# ShifterDial.net
KiCad netlist of a schematic drawn in EAGLE
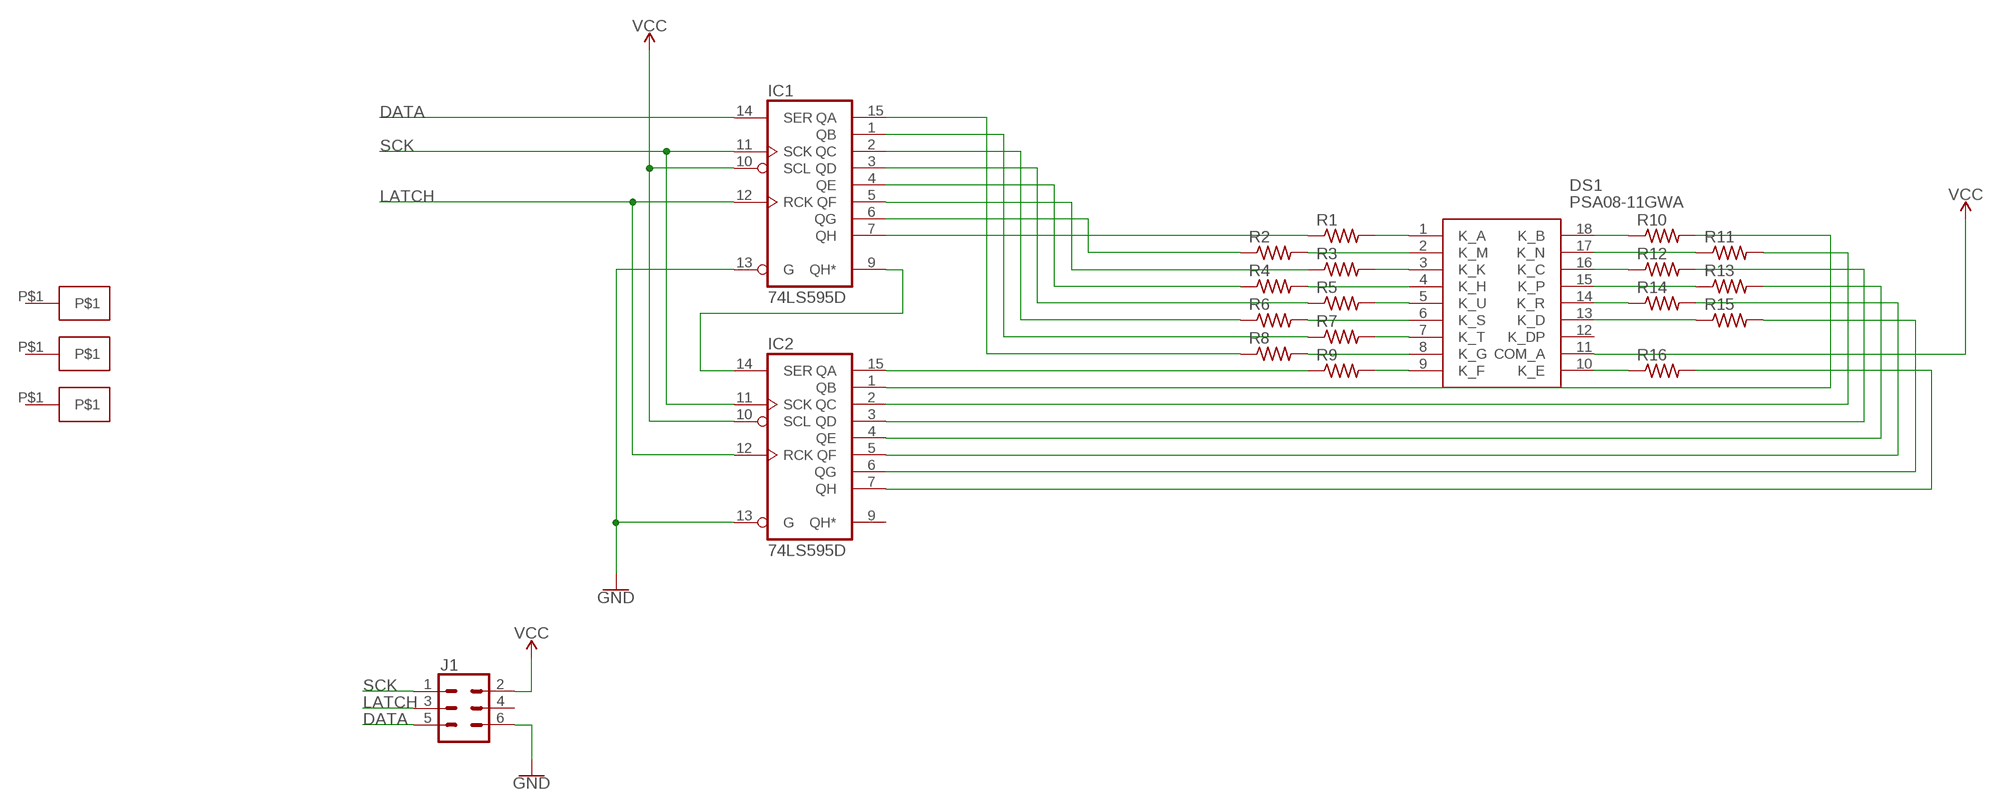
[diagram p0: schematic, sheet 1]

(export (version "E")
  (design (tool "Eeschema 10.0.6"))
  (components
    (comp (ref "DS1")
      (value "PSA08-11GWA")
      (footprint "eagle-import:PSA0811GWA")
      (fields (field (name "MOUSER_PART_NUMBER") "604-PSA08-11GWA"))
      (libsource (lib "eagle-import") (part "PSA08-11GWA"))
    )
    (comp (ref "IC1")
      (value "74LS595D")
      (footprint "eagle-import:SO16")
      (libsource (lib "eagle-import") (part "74595DLS"))
    )
    (comp (ref "IC2")
      (value "74LS595D")
      (footprint "eagle-import:SO16")
      (libsource (lib "eagle-import") (part "74595DLS"))
    )
    (comp (ref "J1")
      (value "CONN_03X2SHROUD")
      (footprint "eagle-import:2X3-SHROUDED")
      (libsource (lib "eagle-import") (part "CONN_03X2SHROUD"))
    )
    (comp (ref "R1")
      (value "R-US_R0603")
      (footprint "eagle-import:R0603")
      (libsource (lib "eagle-import") (part "R-US_R0603"))
    )
    (comp (ref "R2")
      (value "R-US_R0603")
      (footprint "eagle-import:R0603")
      (libsource (lib "eagle-import") (part "R-US_R0603"))
    )
    (comp (ref "R3")
      (value "R-US_R0603")
      (footprint "eagle-import:R0603")
      (libsource (lib "eagle-import") (part "R-US_R0603"))
    )
    (comp (ref "R4")
      (value "R-US_R0603")
      (footprint "eagle-import:R0603")
      (libsource (lib "eagle-import") (part "R-US_R0603"))
    )
    (comp (ref "R5")
      (value "R-US_R0603")
      (footprint "eagle-import:R0603")
      (libsource (lib "eagle-import") (part "R-US_R0603"))
    )
    (comp (ref "R6")
      (value "R-US_R0603")
      (footprint "eagle-import:R0603")
      (libsource (lib "eagle-import") (part "R-US_R0603"))
    )
    (comp (ref "R7")
      (value "R-US_R0603")
      (footprint "eagle-import:R0603")
      (libsource (lib "eagle-import") (part "R-US_R0603"))
    )
    (comp (ref "R8")
      (value "R-US_R0603")
      (footprint "eagle-import:R0603")
      (libsource (lib "eagle-import") (part "R-US_R0603"))
    )
    (comp (ref "R9")
      (value "R-US_R0603")
      (footprint "eagle-import:R0603")
      (libsource (lib "eagle-import") (part "R-US_R0603"))
    )
    (comp (ref "R10")
      (value "R-US_R0603")
      (footprint "eagle-import:R0603")
      (libsource (lib "eagle-import") (part "R-US_R0603"))
    )
    (comp (ref "R11")
      (value "R-US_R0603")
      (footprint "eagle-import:R0603")
      (libsource (lib "eagle-import") (part "R-US_R0603"))
    )
    (comp (ref "R12")
      (value "R-US_R0603")
      (footprint "eagle-import:R0603")
      (libsource (lib "eagle-import") (part "R-US_R0603"))
    )
    (comp (ref "R13")
      (value "R-US_R0603")
      (footprint "eagle-import:R0603")
      (libsource (lib "eagle-import") (part "R-US_R0603"))
    )
    (comp (ref "R14")
      (value "R-US_R0603")
      (footprint "eagle-import:R0603")
      (libsource (lib "eagle-import") (part "R-US_R0603"))
    )
    (comp (ref "R15")
      (value "R-US_R0603")
      (footprint "eagle-import:R0603")
      (libsource (lib "eagle-import") (part "R-US_R0603"))
    )
    (comp (ref "R16")
      (value "R-US_R0603")
      (footprint "eagle-import:R0603")
      (libsource (lib "eagle-import") (part "R-US_R0603"))
    )
    (comp (ref "U$1")
      (value "KEYSTONEM3")
      (footprint "eagle-import:M3SMDSTANDOFF")
      (libsource (lib "eagle-import") (part "KEYSTONEM3"))
    )
    (comp (ref "U$2")
      (value "KEYSTONEM3")
      (footprint "eagle-import:M3SMDSTANDOFF")
      (libsource (lib "eagle-import") (part "KEYSTONEM3"))
    )
    (comp (ref "U$3")
      (value "KEYSTONEM3")
      (footprint "eagle-import:M3SMDSTANDOFF")
      (libsource (lib "eagle-import") (part "KEYSTONEM3"))
    )
  )
  (nets
    (net (code "1") (name "/DATA") (class "Default")
      (node (ref "IC1") (pin "14") (pinfunction "SER_14") (pintype "input"))
      (node (ref "J1") (pin "5") (pinfunction "5_5") (pintype "bidirectional"))
    )
    (net (code "2") (name "/LATCH") (class "Default")
      (node (ref "IC1") (pin "12") (pinfunction "RCK_12") (pintype "input"))
      (node (ref "IC2") (pin "12") (pinfunction "RCK_12") (pintype "input"))
      (node (ref "J1") (pin "3") (pinfunction "3_3") (pintype "bidirectional"))
    )
    (net (code "3") (name "/SCK") (class "Default")
      (node (ref "IC1") (pin "11") (pinfunction "SCK_11") (pintype "input"))
      (node (ref "IC2") (pin "11") (pinfunction "SCK_11") (pintype "input"))
      (node (ref "J1") (pin "1") (pinfunction "1_1") (pintype "bidirectional"))
    )
    (net (code "4") (name "GND") (class "Default")
      (node (ref "IC1") (pin "13") (pinfunction "G_13") (pintype "input"))
      (node (ref "IC2") (pin "13") (pinfunction "G_13") (pintype "input"))
      (node (ref "J1") (pin "6") (pinfunction "6_6") (pintype "bidirectional"))
    )
    (net (code "5") (name "Net-(DS1-K_A)") (class "Default")
      (node (ref "DS1") (pin "1") (pinfunction "K_A_1") (pintype "bidirectional"))
      (node (ref "R1") (pin "2") (pinfunction "2_2") (pintype "passive"))
    )
    (net (code "6") (name "Net-(DS1-K_B)") (class "Default")
      (node (ref "DS1") (pin "18") (pinfunction "K_B_18") (pintype "bidirectional"))
      (node (ref "R10") (pin "1") (pinfunction "1_1") (pintype "passive"))
    )
    (net (code "7") (name "Net-(DS1-K_C)") (class "Default")
      (node (ref "DS1") (pin "16") (pinfunction "K_C_16") (pintype "bidirectional"))
      (node (ref "R12") (pin "1") (pinfunction "1_1") (pintype "passive"))
    )
    (net (code "8") (name "Net-(DS1-K_D)") (class "Default")
      (node (ref "DS1") (pin "13") (pinfunction "K_D_13") (pintype "bidirectional"))
      (node (ref "R15") (pin "1") (pinfunction "1_1") (pintype "passive"))
    )
    (net (code "9") (name "Net-(DS1-K_E)") (class "Default")
      (node (ref "DS1") (pin "10") (pinfunction "K_E_10") (pintype "bidirectional"))
      (node (ref "R16") (pin "1") (pinfunction "1_1") (pintype "passive"))
    )
    (net (code "10") (name "Net-(DS1-K_F)") (class "Default")
      (node (ref "DS1") (pin "9") (pinfunction "K_F_9") (pintype "bidirectional"))
      (node (ref "R9") (pin "2") (pinfunction "2_2") (pintype "passive"))
    )
    (net (code "11") (name "Net-(DS1-K_G)") (class "Default")
      (node (ref "DS1") (pin "8") (pinfunction "K_G_8") (pintype "bidirectional"))
      (node (ref "R8") (pin "2") (pinfunction "2_2") (pintype "passive"))
    )
    (net (code "12") (name "Net-(DS1-K_H)") (class "Default")
      (node (ref "DS1") (pin "4") (pinfunction "K_H_4") (pintype "bidirectional"))
      (node (ref "R4") (pin "2") (pinfunction "2_2") (pintype "passive"))
    )
    (net (code "13") (name "Net-(DS1-K_K)") (class "Default")
      (node (ref "DS1") (pin "3") (pinfunction "K_K_3") (pintype "bidirectional"))
      (node (ref "R3") (pin "2") (pinfunction "2_2") (pintype "passive"))
    )
    (net (code "14") (name "Net-(DS1-K_M)") (class "Default")
      (node (ref "DS1") (pin "2") (pinfunction "K_M_2") (pintype "bidirectional"))
      (node (ref "R2") (pin "2") (pinfunction "2_2") (pintype "passive"))
    )
    (net (code "15") (name "Net-(DS1-K_N)") (class "Default")
      (node (ref "DS1") (pin "17") (pinfunction "K_N_17") (pintype "bidirectional"))
      (node (ref "R11") (pin "1") (pinfunction "1_1") (pintype "passive"))
    )
    (net (code "16") (name "Net-(DS1-K_P)") (class "Default")
      (node (ref "DS1") (pin "15") (pinfunction "K_P_15") (pintype "bidirectional"))
      (node (ref "R13") (pin "1") (pinfunction "1_1") (pintype "passive"))
    )
    (net (code "17") (name "Net-(DS1-K_R)") (class "Default")
      (node (ref "DS1") (pin "14") (pinfunction "K_R_14") (pintype "bidirectional"))
      (node (ref "R14") (pin "1") (pinfunction "1_1") (pintype "passive"))
    )
    (net (code "18") (name "Net-(DS1-K_S)") (class "Default")
      (node (ref "DS1") (pin "6") (pinfunction "K_S_6") (pintype "bidirectional"))
      (node (ref "R6") (pin "2") (pinfunction "2_2") (pintype "passive"))
    )
    (net (code "19") (name "Net-(DS1-K_T)") (class "Default")
      (node (ref "DS1") (pin "7") (pinfunction "K_T_7") (pintype "bidirectional"))
      (node (ref "R7") (pin "2") (pinfunction "2_2") (pintype "passive"))
    )
    (net (code "20") (name "Net-(DS1-K_U)") (class "Default")
      (node (ref "DS1") (pin "5") (pinfunction "K_U_5") (pintype "bidirectional"))
      (node (ref "R5") (pin "2") (pinfunction "2_2") (pintype "passive"))
    )
    (net (code "21") (name "Net-(IC1A-QA)") (class "Default")
      (node (ref "IC1") (pin "15") (pinfunction "QA_15") (pintype "tri_state"))
      (node (ref "R8") (pin "1") (pinfunction "1_1") (pintype "passive"))
    )
    (net (code "22") (name "Net-(IC1A-QB)") (class "Default")
      (node (ref "IC1") (pin "1") (pinfunction "QB_1") (pintype "tri_state"))
      (node (ref "R7") (pin "1") (pinfunction "1_1") (pintype "passive"))
    )
    (net (code "23") (name "Net-(IC1A-QC)") (class "Default")
      (node (ref "IC1") (pin "2") (pinfunction "QC_2") (pintype "tri_state"))
      (node (ref "R6") (pin "1") (pinfunction "1_1") (pintype "passive"))
    )
    (net (code "24") (name "Net-(IC1A-QD)") (class "Default")
      (node (ref "IC1") (pin "3") (pinfunction "QD_3") (pintype "tri_state"))
      (node (ref "R5") (pin "1") (pinfunction "1_1") (pintype "passive"))
    )
    (net (code "25") (name "Net-(IC1A-QE)") (class "Default")
      (node (ref "IC1") (pin "4") (pinfunction "QE_4") (pintype "tri_state"))
      (node (ref "R4") (pin "1") (pinfunction "1_1") (pintype "passive"))
    )
    (net (code "26") (name "Net-(IC1A-QF)") (class "Default")
      (node (ref "IC1") (pin "5") (pinfunction "QF_5") (pintype "tri_state"))
      (node (ref "R3") (pin "1") (pinfunction "1_1") (pintype "passive"))
    )
    (net (code "27") (name "Net-(IC1A-QG)") (class "Default")
      (node (ref "IC1") (pin "6") (pinfunction "QG_6") (pintype "tri_state"))
      (node (ref "R2") (pin "1") (pinfunction "1_1") (pintype "passive"))
    )
    (net (code "28") (name "Net-(IC1A-QH)") (class "Default")
      (node (ref "IC1") (pin "7") (pinfunction "QH_7") (pintype "tri_state"))
      (node (ref "R1") (pin "1") (pinfunction "1_1") (pintype "passive"))
    )
    (net (code "29") (name "Net-(IC1A-QH*)") (class "Default")
      (node (ref "IC1") (pin "9") (pinfunction "QH*_9") (pintype "tri_state"))
      (node (ref "IC2") (pin "14") (pinfunction "SER_14") (pintype "input"))
    )
    (net (code "30") (name "Net-(IC2A-QA)") (class "Default")
      (node (ref "IC2") (pin "15") (pinfunction "QA_15") (pintype "tri_state"))
      (node (ref "R9") (pin "1") (pinfunction "1_1") (pintype "passive"))
    )
    (net (code "31") (name "Net-(IC2A-QB)") (class "Default")
      (node (ref "IC2") (pin "1") (pinfunction "QB_1") (pintype "tri_state"))
      (node (ref "R10") (pin "2") (pinfunction "2_2") (pintype "passive"))
    )
    (net (code "32") (name "Net-(IC2A-QC)") (class "Default")
      (node (ref "IC2") (pin "2") (pinfunction "QC_2") (pintype "tri_state"))
      (node (ref "R11") (pin "2") (pinfunction "2_2") (pintype "passive"))
    )
    (net (code "33") (name "Net-(IC2A-QD)") (class "Default")
      (node (ref "IC2") (pin "3") (pinfunction "QD_3") (pintype "tri_state"))
      (node (ref "R12") (pin "2") (pinfunction "2_2") (pintype "passive"))
    )
    (net (code "34") (name "Net-(IC2A-QE)") (class "Default")
      (node (ref "IC2") (pin "4") (pinfunction "QE_4") (pintype "tri_state"))
      (node (ref "R13") (pin "2") (pinfunction "2_2") (pintype "passive"))
    )
    (net (code "35") (name "Net-(IC2A-QF)") (class "Default")
      (node (ref "IC2") (pin "5") (pinfunction "QF_5") (pintype "tri_state"))
      (node (ref "R14") (pin "2") (pinfunction "2_2") (pintype "passive"))
    )
    (net (code "36") (name "Net-(IC2A-QG)") (class "Default")
      (node (ref "IC2") (pin "6") (pinfunction "QG_6") (pintype "tri_state"))
      (node (ref "R15") (pin "2") (pinfunction "2_2") (pintype "passive"))
    )
    (net (code "37") (name "Net-(IC2A-QH)") (class "Default")
      (node (ref "IC2") (pin "7") (pinfunction "QH_7") (pintype "tri_state"))
      (node (ref "R16") (pin "2") (pinfunction "2_2") (pintype "passive"))
    )
    (net (code "38") (name "VCC") (class "Default")
      (node (ref "DS1") (pin "11") (pinfunction "COM_A_11") (pintype "bidirectional"))
      (node (ref "IC1") (pin "10") (pinfunction "SCL_10") (pintype "input"))
      (node (ref "IC2") (pin "10") (pinfunction "SCL_10") (pintype "input"))
      (node (ref "J1") (pin "2") (pinfunction "2_2") (pintype "bidirectional"))
    )
    (net (code "39") (name "unconnected-(DS1-K_DP-Pad12)") (class "Default")
      (node (ref "DS1") (pin "12") (pinfunction "K_DP_12") (pintype "bidirectional"))
    )
    (net (code "40") (name "unconnected-(IC2A-QH*-Pad9)") (class "Default")
      (node (ref "IC2") (pin "9") (pinfunction "QH*_9") (pintype "tri_state"))
    )
    (net (code "41") (name "unconnected-(J1-Pad4)") (class "Default")
      (node (ref "J1") (pin "4") (pinfunction "4_4") (pintype "bidirectional"))
    )
    (net (code "42") (name "unconnected-(U$1-PadP$1)") (class "Default")
      (node (ref "U$1") (pin "P$1") (pinfunction "P$1_P$1") (pintype "bidirectional"))
    )
    (net (code "43") (name "unconnected-(U$2-PadP$1)") (class "Default")
      (node (ref "U$2") (pin "P$1") (pinfunction "P$1_P$1") (pintype "bidirectional"))
    )
    (net (code "44") (name "unconnected-(U$3-PadP$1)") (class "Default")
      (node (ref "U$3") (pin "P$1") (pinfunction "P$1_P$1") (pintype "bidirectional"))
    )
  )
)
